# C128_Ultimate.net
KiCad netlist of a schematic drawn in EAGLE
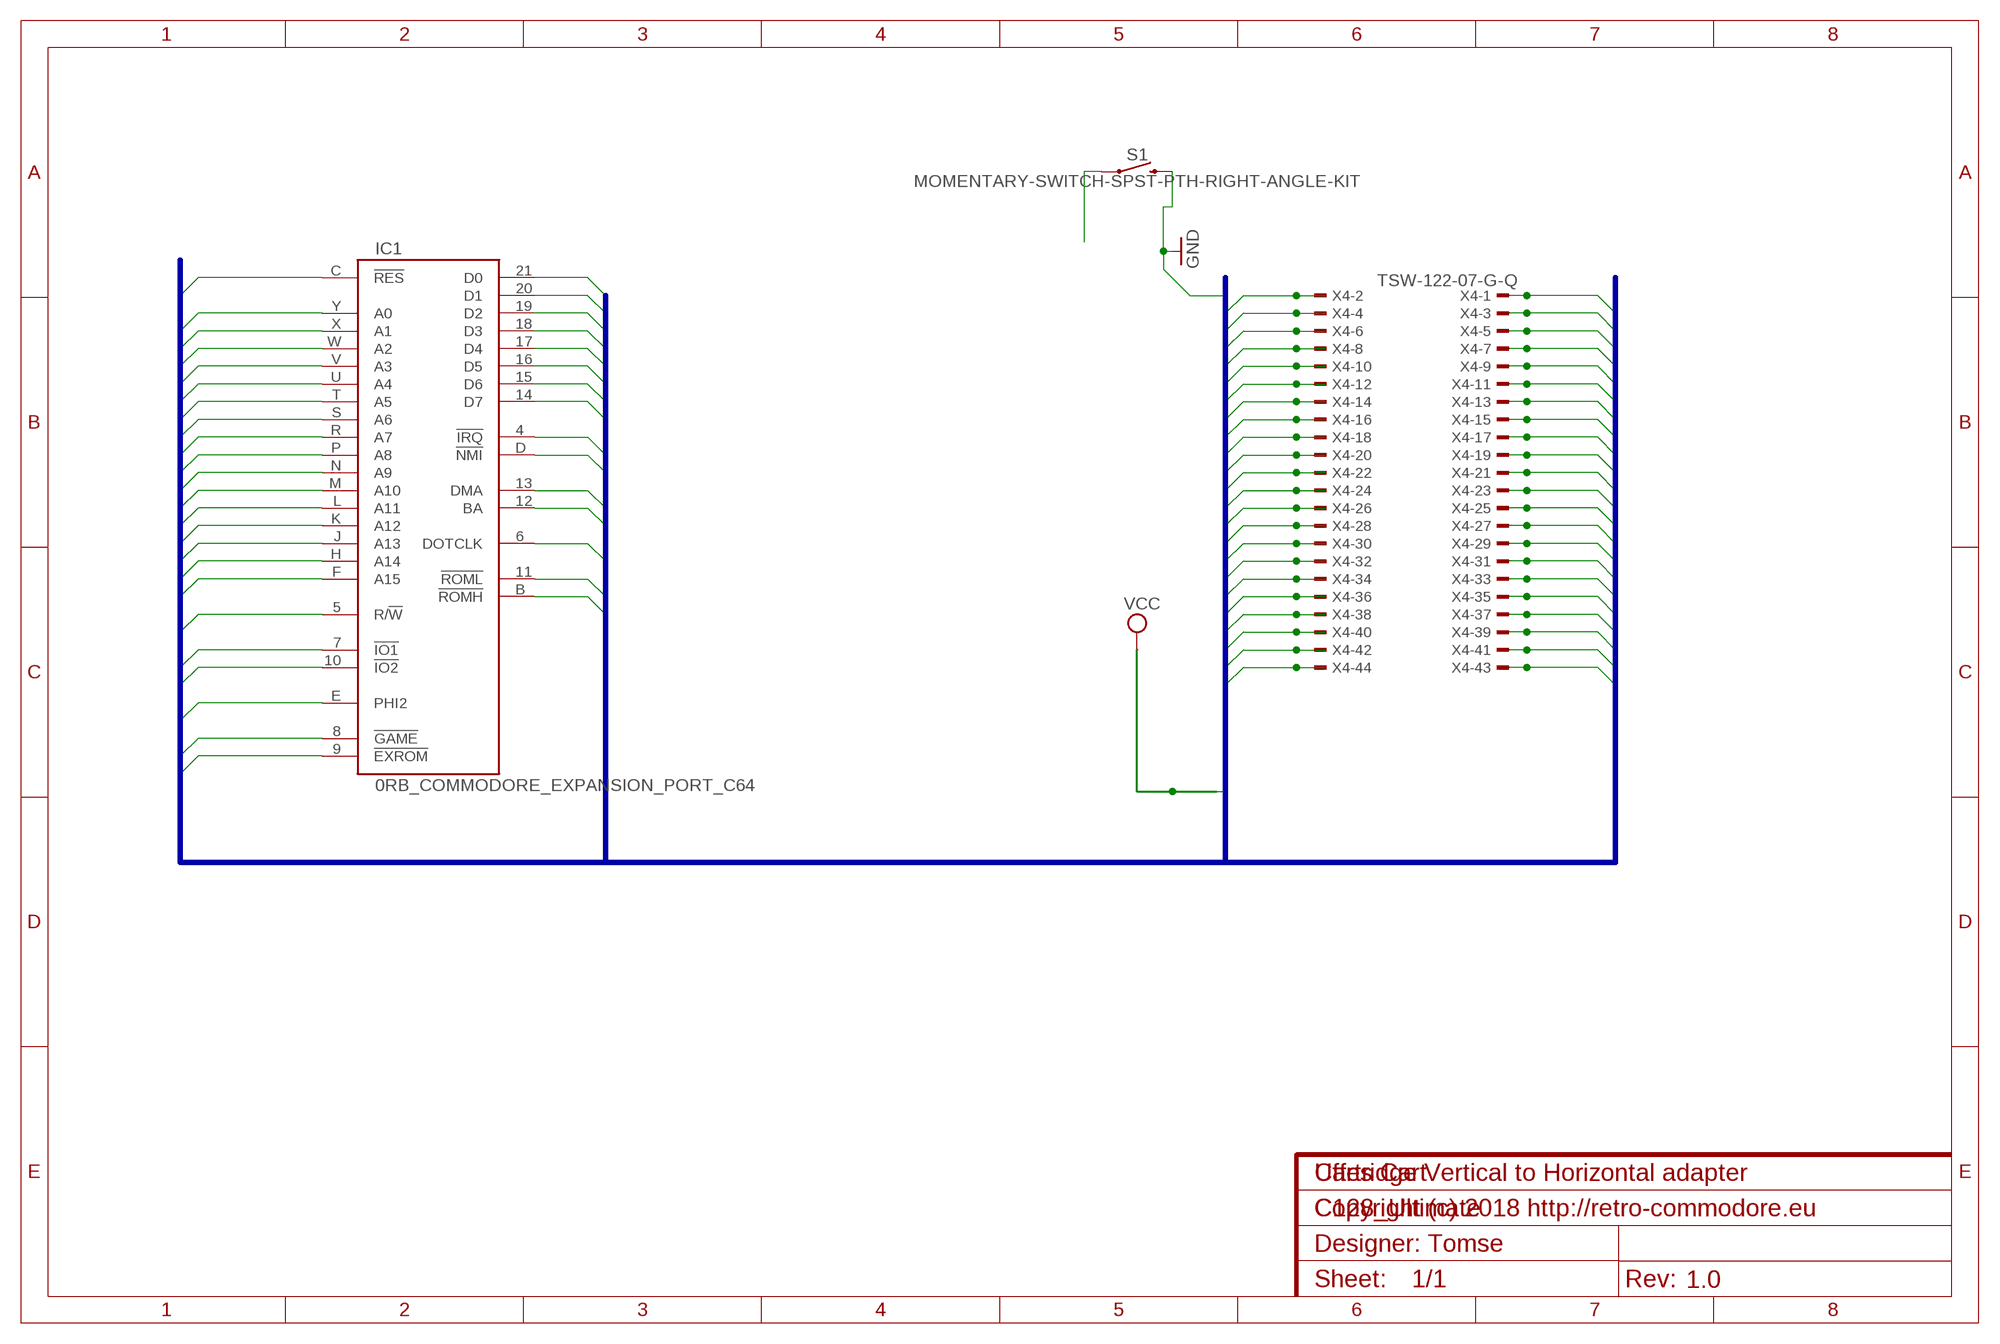
[diagram p0: schematic, sheet 1]

(export (version "E")
  (design (tool "Eeschema 10.0.6"))
  (components
    (comp (ref "IC1")
      (value "0RB_COMMODORE_EXPANSION_PORT_C64")
      (footprint "eagle-import:0RB_COMMODORE_MA100-22-2")
      (libsource (lib "eagle-import") (part "0RB_COMMODORE_EXPANSION_PORT_C64"))
    )
    (comp (ref "S1")
      (value "MOMENTARY-SWITCH-SPST-PTH-RIGHT-ANGLE-KIT")
      (footprint "eagle-import:TACTILE_SWITCH_PTH_RIGHT_ANGLE_KIT")
      (libsource (lib "eagle-import") (part "MOMENTARY-SWITCH-SPST-PTH-RIGHT-ANGLE-KIT"))
    )
    (comp (ref "X4")
      (value "TSW-122-07-G-Q")
      (footprint "eagle-import:TSW-122-XX-G-Q")
      (fields (field (name "MF") "Samtec Inc."))
      (libsource (lib "eagle-import") (part "TSW-122--G-Q07"))
    )
  )
  (nets
    (net (code "1") (name "/A0") (class "Default")
      (node (ref "IC1") (pin "Y") (pinfunction "A0_Y") (pintype "bidirectional"))
      (node (ref "X4") (pin "41") (pinfunction "1_41") (pintype "passive"))
    )
    (net (code "2") (name "/A1") (class "Default")
      (node (ref "IC1") (pin "X") (pinfunction "A1_X") (pintype "bidirectional"))
      (node (ref "X4") (pin "39") (pinfunction "1_39") (pintype "passive"))
    )
    (net (code "3") (name "/A2") (class "Default")
      (node (ref "IC1") (pin "W") (pinfunction "A2_W") (pintype "bidirectional"))
      (node (ref "X4") (pin "37") (pinfunction "1_37") (pintype "passive"))
    )
    (net (code "4") (name "/A3") (class "Default")
      (node (ref "IC1") (pin "V") (pinfunction "A3_V") (pintype "bidirectional"))
      (node (ref "X4") (pin "35") (pinfunction "1_35") (pintype "passive"))
    )
    (net (code "5") (name "/A4") (class "Default")
      (node (ref "IC1") (pin "U") (pinfunction "A4_U") (pintype "bidirectional"))
      (node (ref "X4") (pin "33") (pinfunction "1_33") (pintype "passive"))
    )
    (net (code "6") (name "/A5") (class "Default")
      (node (ref "IC1") (pin "T") (pinfunction "A5_T") (pintype "bidirectional"))
      (node (ref "X4") (pin "31") (pinfunction "1_31") (pintype "passive"))
    )
    (net (code "7") (name "/A6") (class "Default")
      (node (ref "IC1") (pin "S") (pinfunction "A6_S") (pintype "bidirectional"))
      (node (ref "X4") (pin "29") (pinfunction "1_29") (pintype "passive"))
    )
    (net (code "8") (name "/A7") (class "Default")
      (node (ref "IC1") (pin "R") (pinfunction "A7_R") (pintype "bidirectional"))
      (node (ref "X4") (pin "27") (pinfunction "1_27") (pintype "passive"))
    )
    (net (code "9") (name "/A8") (class "Default")
      (node (ref "IC1") (pin "P") (pinfunction "A8_P") (pintype "bidirectional"))
      (node (ref "X4") (pin "25") (pinfunction "1_25") (pintype "passive"))
    )
    (net (code "10") (name "/A9") (class "Default")
      (node (ref "IC1") (pin "N") (pinfunction "A9_N") (pintype "bidirectional"))
      (node (ref "X4") (pin "23") (pinfunction "1_23") (pintype "passive"))
    )
    (net (code "11") (name "/A10") (class "Default")
      (node (ref "IC1") (pin "M") (pinfunction "A10_M") (pintype "bidirectional"))
      (node (ref "X4") (pin "21") (pinfunction "1_21") (pintype "passive"))
    )
    (net (code "12") (name "/A11") (class "Default")
      (node (ref "IC1") (pin "L") (pinfunction "A11_L") (pintype "bidirectional"))
      (node (ref "X4") (pin "19") (pinfunction "1_19") (pintype "passive"))
    )
    (net (code "13") (name "/A12") (class "Default")
      (node (ref "IC1") (pin "K") (pinfunction "A12_K") (pintype "bidirectional"))
      (node (ref "X4") (pin "17") (pinfunction "1_17") (pintype "passive"))
    )
    (net (code "14") (name "/A13") (class "Default")
      (node (ref "IC1") (pin "J") (pinfunction "A13_J") (pintype "bidirectional"))
      (node (ref "X4") (pin "15") (pinfunction "1_15") (pintype "passive"))
    )
    (net (code "15") (name "/A14") (class "Default")
      (node (ref "IC1") (pin "H") (pinfunction "A14_H") (pintype "bidirectional"))
      (node (ref "X4") (pin "13") (pinfunction "1_13") (pintype "passive"))
    )
    (net (code "16") (name "/A15") (class "Default")
      (node (ref "IC1") (pin "F") (pinfunction "A15_F") (pintype "bidirectional"))
      (node (ref "X4") (pin "11") (pinfunction "1_11") (pintype "passive"))
    )
    (net (code "17") (name "/BA") (class "Default")
      (node (ref "IC1") (pin "12") (pinfunction "BA_12") (pintype "output"))
      (node (ref "X4") (pin "24") (pinfunction "1_24") (pintype "passive"))
    )
    (net (code "18") (name "/D0") (class "Default")
      (node (ref "IC1") (pin "21") (pinfunction "D0_21") (pintype "bidirectional"))
      (node (ref "X4") (pin "42") (pinfunction "1_42") (pintype "passive"))
    )
    (net (code "19") (name "/D1") (class "Default")
      (node (ref "IC1") (pin "20") (pinfunction "D1_20") (pintype "bidirectional"))
      (node (ref "X4") (pin "40") (pinfunction "1_40") (pintype "passive"))
    )
    (net (code "20") (name "/D2") (class "Default")
      (node (ref "IC1") (pin "19") (pinfunction "D2_19") (pintype "bidirectional"))
      (node (ref "X4") (pin "38") (pinfunction "1_38") (pintype "passive"))
    )
    (net (code "21") (name "/D3") (class "Default")
      (node (ref "IC1") (pin "18") (pinfunction "D3_18") (pintype "bidirectional"))
      (node (ref "X4") (pin "36") (pinfunction "1_36") (pintype "passive"))
    )
    (net (code "22") (name "/D4") (class "Default")
      (node (ref "IC1") (pin "17") (pinfunction "D4_17") (pintype "bidirectional"))
      (node (ref "X4") (pin "34") (pinfunction "1_34") (pintype "passive"))
    )
    (net (code "23") (name "/D5") (class "Default")
      (node (ref "IC1") (pin "16") (pinfunction "D5_16") (pintype "bidirectional"))
      (node (ref "X4") (pin "32") (pinfunction "1_32") (pintype "passive"))
    )
    (net (code "24") (name "/D6") (class "Default")
      (node (ref "IC1") (pin "15") (pinfunction "D6_15") (pintype "bidirectional"))
      (node (ref "X4") (pin "30") (pinfunction "1_30") (pintype "passive"))
    )
    (net (code "25") (name "/D7") (class "Default")
      (node (ref "IC1") (pin "14") (pinfunction "D7_14") (pintype "bidirectional"))
      (node (ref "X4") (pin "28") (pinfunction "1_28") (pintype "passive"))
    )
    (net (code "26") (name "/DOTCLK") (class "Default")
      (node (ref "IC1") (pin "6") (pinfunction "DOTCLK_6") (pintype "output"))
      (node (ref "X4") (pin "12") (pinfunction "1_12") (pintype "passive"))
    )
    (net (code "27") (name "/PHI2") (class "Default")
      (node (ref "IC1") (pin "E") (pinfunction "PHI2_E") (pintype "output"))
      (node (ref "X4") (pin "9") (pinfunction "1_9") (pintype "passive"))
    )
    (net (code "28") (name "/R~{W}") (class "Default")
      (node (ref "IC1") (pin "5") (pinfunction "R/~{W}_5") (pintype "bidirectional"))
      (node (ref "X4") (pin "10") (pinfunction "1_10") (pintype "passive"))
    )
    (net (code "29") (name "/~{DMA}") (class "Default")
      (node (ref "IC1") (pin "13") (pinfunction "DMA_13") (pintype "passive"))
      (node (ref "X4") (pin "26") (pinfunction "1_26") (pintype "passive"))
    )
    (net (code "30") (name "/~{EXROM}") (class "Default")
      (node (ref "IC1") (pin "9") (pinfunction "~{EXROM}_9") (pintype "passive"))
      (node (ref "X4") (pin "18") (pinfunction "1_18") (pintype "passive"))
    )
    (net (code "31") (name "/~{GAME}") (class "Default")
      (node (ref "IC1") (pin "8") (pinfunction "~{GAME}_8") (pintype "passive"))
      (node (ref "X4") (pin "16") (pinfunction "1_16") (pintype "passive"))
    )
    (net (code "32") (name "/~{IO1}") (class "Default")
      (node (ref "IC1") (pin "7") (pinfunction "~{IO1}_7") (pintype "output"))
      (node (ref "X4") (pin "14") (pinfunction "1_14") (pintype "passive"))
    )
    (net (code "33") (name "/~{IO2}") (class "Default")
      (node (ref "IC1") (pin "10") (pinfunction "~{IO2}_10") (pintype "output"))
      (node (ref "X4") (pin "20") (pinfunction "1_20") (pintype "passive"))
    )
    (net (code "34") (name "/~{IRQ}") (class "Default")
      (node (ref "IC1") (pin "4") (pinfunction "~{IRQ}_4") (pintype "passive"))
      (node (ref "X4") (pin "8") (pinfunction "1_8") (pintype "passive"))
    )
    (net (code "35") (name "/~{NMI}") (class "Default")
      (node (ref "IC1") (pin "D") (pinfunction "~{NMI}_D") (pintype "passive"))
      (node (ref "X4") (pin "7") (pinfunction "1_7") (pintype "passive"))
    )
    (net (code "36") (name "/~{RES}") (class "Default")
      (node (ref "IC1") (pin "C") (pinfunction "~{RES}_C") (pintype "passive"))
      (node (ref "S1") (pin "1") (pinfunction "1_1") (pintype "passive"))
      (node (ref "X4") (pin "5") (pinfunction "1_5") (pintype "passive"))
    )
    (net (code "37") (name "/~{ROMH}") (class "Default")
      (node (ref "IC1") (pin "B") (pinfunction "~{ROMH}_B") (pintype "output"))
      (node (ref "X4") (pin "3") (pinfunction "1_3") (pintype "passive"))
    )
    (net (code "38") (name "/~{ROML}") (class "Default")
      (node (ref "IC1") (pin "11") (pinfunction "~{ROML}_11") (pintype "output"))
      (node (ref "X4") (pin "22") (pinfunction "1_22") (pintype "passive"))
    )
    (net (code "39") (name "GND") (class "Default")
      (node (ref "S1") (pin "2") (pinfunction "2_2") (pintype "passive"))
      (node (ref "X4") (pin "1") (pinfunction "1_1") (pintype "passive"))
      (node (ref "X4") (pin "2") (pinfunction "1_2") (pintype "passive"))
      (node (ref "X4") (pin "43") (pinfunction "1_43") (pintype "passive"))
      (node (ref "X4") (pin "44") (pinfunction "1_44") (pintype "passive"))
    )
    (net (code "40") (name "VCC") (class "Default")
      (node (ref "X4") (pin "4") (pinfunction "1_4") (pintype "passive"))
      (node (ref "X4") (pin "6") (pinfunction "1_6") (pintype "passive"))
    )
  )
)
